# SDConnection.net
KiCad netlist of a schematic drawn in Altium Designer
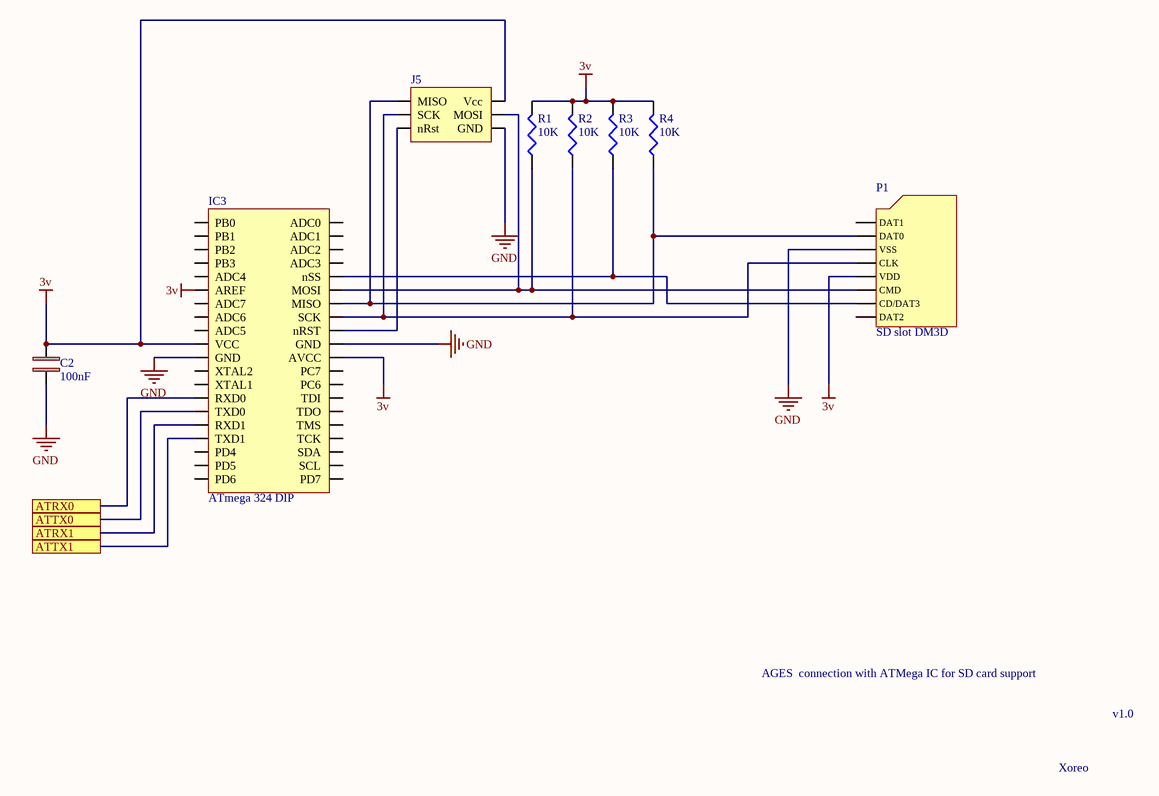
[diagram p0: SDConnection.SchDoc]

(export (version "E")
  (design (tool "Eeschema 10.0.6"))
  (components
    (comp (ref "C2")
      (value "100nF")
      (footprint "CAPACITOR 1206")
      (description "Ceramic capacitor SMD-1206 100nF /50V X7R# K +-10%, AVX, RoHS, /4000 reel/")
      (fields
        (field (name "MANUFACTURER") "Kyocera AVX")
        (field (name "MANUFACTURER PART NUMBER") "12065C104KAT2A")
      )
      (libsource (lib "SD-Module-SCH-LIB") (part "Capacitor{colon} 100nF"))
    )
    (comp (ref "IC3")
      (value "ATmega 324 DIP")
      (footprint "DIP40 HDR")
      (description "8-bit AVR MCU, 32 KB, 2048 Bytes, 20 MHz, 1.8 to 5.5V, PDIP-40, RoHS")
      (fields
        (field (name "MANUFACTURER") "Microchip")
        (field (name "MANUFACTURER PART NUMBER") "ATMEGA324PA-PU")
      )
      (libsource (lib "SD-Module-SCH-LIB") (part "IC{colon} ATmega324"))
    )
    (comp (ref "J5")
      (value "2x3 male pin header")
      (footprint "2X3 HDR")
      (description "2x3 Pin header")
      (libsource (lib "SD-Module-SCH-LIB") (part "Connector{colon} 2x3 Pin"))
    )
    (comp (ref "P1")
      (value "SD slot DM3D")
      (footprint "SD SLOT")
      (description "Memory Card Connectors MICRO SD CD CONN STD SMT PUSHPULL")
      (fields (field (name "MANUFACTURER") "Hirose") (field (name "MANUFACTURER PART NUMBER") "DM3D-SF"))
      (libsource (lib "SD-Module-SCH-LIB") (part "SD slot"))
    )
    (comp (ref "R1")
      (value "10K")
      (footprint "RESISTOR 0805")
      (description "Res Thick Film 0805 10K Ohm 5% 1/8W ±200ppm/°C Molded SMD SMD Paper T/R")
      (fields
        (field (name "MANUFACTURER") "Vishay Dale")
        (field (name "MANUFACTURER PART NUMBER") "CRCW080510K0JNEB")
      )
      (libsource (lib "SD-Module-SCH-LIB") (part "Resistor{colon} 10K R"))
    )
    (comp (ref "R2")
      (value "10K")
      (footprint "RESISTOR 0805")
      (description "Res Thick Film 0805 10K Ohm 5% 1/8W ±200ppm/°C Molded SMD SMD Paper T/R")
      (fields
        (field (name "MANUFACTURER") "Vishay Dale")
        (field (name "MANUFACTURER PART NUMBER") "CRCW080510K0JNEB")
      )
      (libsource (lib "SD-Module-SCH-LIB") (part "Resistor{colon} 10K R"))
    )
    (comp (ref "R3")
      (value "10K")
      (footprint "RESISTOR 0805")
      (description "Res Thick Film 0805 10K Ohm 5% 1/8W ±200ppm/°C Molded SMD SMD Paper T/R")
      (fields
        (field (name "MANUFACTURER") "Vishay Dale")
        (field (name "MANUFACTURER PART NUMBER") "CRCW080510K0JNEB")
      )
      (libsource (lib "SD-Module-SCH-LIB") (part "Resistor{colon} 10K R"))
    )
    (comp (ref "R4")
      (value "10K")
      (footprint "RESISTOR 0805")
      (description "Res Thick Film 0805 10K Ohm 5% 1/8W ±200ppm/°C Molded SMD SMD Paper T/R")
      (fields
        (field (name "MANUFACTURER") "Vishay Dale")
        (field (name "MANUFACTURER PART NUMBER") "CRCW080510K0JNEB")
      )
      (libsource (lib "SD-Module-SCH-LIB") (part "Resistor{colon} 10K R"))
    )
  )
  (nets
    (net (code "1") (name "/ATRX0") (class "Default")
      (node (ref "IC3") (pin "14") (pinfunction "RXD0_14") (pintype "passive"))
    )
    (net (code "2") (name "/ATRX1") (class "Default")
      (node (ref "IC3") (pin "16") (pinfunction "RXD1_16") (pintype "passive"))
    )
    (net (code "3") (name "/ATTX0") (class "Default")
      (node (ref "IC3") (pin "15") (pinfunction "TXD0_15") (pintype "passive"))
    )
    (net (code "4") (name "/ATTX1") (class "Default")
      (node (ref "IC3") (pin "17") (pinfunction "TXD1_17") (pintype "passive"))
    )
    (net (code "5") (name "3v") (class "Default")
      (node (ref "C2") (pin "1") (pinfunction "1_1") (pintype "passive"))
      (node (ref "IC3") (pin "10") (pinfunction "VCC_10") (pintype "passive"))
      (node (ref "IC3") (pin "30") (pinfunction "AVCC_30") (pintype "passive"))
      (node (ref "IC3") (pin "32") (pinfunction "AREF_32") (pintype "passive"))
      (node (ref "J5") (pin "2") (pinfunction "Vcc_2") (pintype "passive"))
      (node (ref "P1") (pin "4") (pinfunction "VDD_4") (pintype "passive"))
      (node (ref "R1") (pin "2") (pinfunction "2_2") (pintype "passive"))
      (node (ref "R2") (pin "2") (pinfunction "2_2") (pintype "passive"))
      (node (ref "R3") (pin "2") (pinfunction "2_2") (pintype "passive"))
      (node (ref "R4") (pin "2") (pinfunction "2_2") (pintype "passive"))
    )
    (net (code "6") (name "GND") (class "Default")
      (node (ref "C2") (pin "2") (pinfunction "2_2") (pintype "passive"))
      (node (ref "IC3") (pin "11") (pinfunction "GND_11") (pintype "passive"))
      (node (ref "IC3") (pin "31") (pinfunction "GND_31") (pintype "passive"))
      (node (ref "J5") (pin "6") (pinfunction "GND_6") (pintype "passive"))
      (node (ref "P1") (pin "6") (pinfunction "VSS_6") (pintype "passive"))
    )
    (net (code "7") (name "Net-(IC3-MISO)") (class "Default")
      (node (ref "IC3") (pin "7") (pinfunction "MISO_7") (pintype "passive"))
      (node (ref "J5") (pin "1") (pinfunction "MISO_1") (pintype "passive"))
      (node (ref "P1") (pin "7") (pinfunction "DAT0_7") (pintype "passive"))
      (node (ref "R4") (pin "1") (pinfunction "1_1") (pintype "passive"))
    )
    (net (code "8") (name "Net-(IC3-MOSI)") (class "Default")
      (node (ref "IC3") (pin "6") (pinfunction "MOSI_6") (pintype "passive"))
      (node (ref "J5") (pin "4") (pinfunction "MOSI_4") (pintype "passive"))
      (node (ref "P1") (pin "3") (pinfunction "CMD_3") (pintype "passive"))
      (node (ref "R1") (pin "1") (pinfunction "1_1") (pintype "passive"))
    )
    (net (code "9") (name "Net-(IC3-SCK)") (class "Default")
      (node (ref "IC3") (pin "8") (pinfunction "SCK_8") (pintype "passive"))
      (node (ref "J5") (pin "3") (pinfunction "SCK_3") (pintype "passive"))
      (node (ref "P1") (pin "5") (pinfunction "CLK_5") (pintype "passive"))
      (node (ref "R2") (pin "1") (pinfunction "1_1") (pintype "passive"))
    )
    (net (code "10") (name "Net-(IC3-nRST)") (class "Default")
      (node (ref "IC3") (pin "9") (pinfunction "nRST_9") (pintype "passive"))
      (node (ref "J5") (pin "5") (pinfunction "nRst_5") (pintype "passive"))
    )
    (net (code "11") (name "Net-(IC3-nSS)") (class "Default")
      (node (ref "IC3") (pin "5") (pinfunction "nSS_5") (pintype "passive"))
      (node (ref "P1") (pin "2") (pinfunction "CD/DAT3_2") (pintype "passive"))
      (node (ref "R3") (pin "1") (pinfunction "1_1") (pintype "passive"))
    )
    (net (code "12") (name "unconnected-(IC3-ADC0-Pad40)") (class "Default")
      (node (ref "IC3") (pin "40") (pinfunction "ADC0_40") (pintype "passive"))
    )
    (net (code "13") (name "unconnected-(IC3-ADC1-Pad39)") (class "Default")
      (node (ref "IC3") (pin "39") (pinfunction "ADC1_39") (pintype "passive"))
    )
    (net (code "14") (name "unconnected-(IC3-ADC2-Pad38)") (class "Default")
      (node (ref "IC3") (pin "38") (pinfunction "ADC2_38") (pintype "passive"))
    )
    (net (code "15") (name "unconnected-(IC3-ADC3-Pad37)") (class "Default")
      (node (ref "IC3") (pin "37") (pinfunction "ADC3_37") (pintype "passive"))
    )
    (net (code "16") (name "unconnected-(IC3-ADC4-Pad36)") (class "Default")
      (node (ref "IC3") (pin "36") (pinfunction "ADC4_36") (pintype "passive"))
    )
    (net (code "17") (name "unconnected-(IC3-ADC5-Pad35)") (class "Default")
      (node (ref "IC3") (pin "35") (pinfunction "ADC5_35") (pintype "passive"))
    )
    (net (code "18") (name "unconnected-(IC3-ADC6-Pad34)") (class "Default")
      (node (ref "IC3") (pin "34") (pinfunction "ADC6_34") (pintype "passive"))
    )
    (net (code "19") (name "unconnected-(IC3-ADC7-Pad33)") (class "Default")
      (node (ref "IC3") (pin "33") (pinfunction "ADC7_33") (pintype "passive"))
    )
    (net (code "20") (name "unconnected-(IC3-PB0-Pad1)") (class "Default")
      (node (ref "IC3") (pin "1") (pinfunction "PB0_1") (pintype "passive"))
    )
    (net (code "21") (name "unconnected-(IC3-PB1-Pad2)") (class "Default")
      (node (ref "IC3") (pin "2") (pinfunction "PB1_2") (pintype "passive"))
    )
    (net (code "22") (name "unconnected-(IC3-PB2-Pad3)") (class "Default")
      (node (ref "IC3") (pin "3") (pinfunction "PB2_3") (pintype "passive"))
    )
    (net (code "23") (name "unconnected-(IC3-PB3-Pad4)") (class "Default")
      (node (ref "IC3") (pin "4") (pinfunction "PB3_4") (pintype "passive"))
    )
    (net (code "24") (name "unconnected-(IC3-PC6-Pad28)") (class "Default")
      (node (ref "IC3") (pin "28") (pinfunction "PC6_28") (pintype "passive"))
    )
    (net (code "25") (name "unconnected-(IC3-PC7-Pad29)") (class "Default")
      (node (ref "IC3") (pin "29") (pinfunction "PC7_29") (pintype "passive"))
    )
    (net (code "26") (name "unconnected-(IC3-PD4-Pad18)") (class "Default")
      (node (ref "IC3") (pin "18") (pinfunction "PD4_18") (pintype "passive"))
    )
    (net (code "27") (name "unconnected-(IC3-PD5-Pad19)") (class "Default")
      (node (ref "IC3") (pin "19") (pinfunction "PD5_19") (pintype "passive"))
    )
    (net (code "28") (name "unconnected-(IC3-PD6-Pad20)") (class "Default")
      (node (ref "IC3") (pin "20") (pinfunction "PD6_20") (pintype "passive"))
    )
    (net (code "29") (name "unconnected-(IC3-PD7-Pad21)") (class "Default")
      (node (ref "IC3") (pin "21") (pinfunction "PD7_21") (pintype "passive"))
    )
    (net (code "30") (name "unconnected-(IC3-SCL-Pad22)") (class "Default")
      (node (ref "IC3") (pin "22") (pinfunction "SCL_22") (pintype "passive"))
    )
    (net (code "31") (name "unconnected-(IC3-SDA-Pad23)") (class "Default")
      (node (ref "IC3") (pin "23") (pinfunction "SDA_23") (pintype "passive"))
    )
    (net (code "32") (name "unconnected-(IC3-TCK-Pad24)") (class "Default")
      (node (ref "IC3") (pin "24") (pinfunction "TCK_24") (pintype "passive"))
    )
    (net (code "33") (name "unconnected-(IC3-TDI-Pad27)") (class "Default")
      (node (ref "IC3") (pin "27") (pinfunction "TDI_27") (pintype "passive"))
    )
    (net (code "34") (name "unconnected-(IC3-TDO-Pad26)") (class "Default")
      (node (ref "IC3") (pin "26") (pinfunction "TDO_26") (pintype "passive"))
    )
    (net (code "35") (name "unconnected-(IC3-TMS-Pad25)") (class "Default")
      (node (ref "IC3") (pin "25") (pinfunction "TMS_25") (pintype "passive"))
    )
    (net (code "36") (name "unconnected-(IC3-XTAL1-Pad13)") (class "Default")
      (node (ref "IC3") (pin "13") (pinfunction "XTAL1_13") (pintype "passive"))
    )
    (net (code "37") (name "unconnected-(IC3-XTAL2-Pad12)") (class "Default")
      (node (ref "IC3") (pin "12") (pinfunction "XTAL2_12") (pintype "passive"))
    )
    (net (code "38") (name "unconnected-(P1-DAT1-Pad8)") (class "Default")
      (node (ref "P1") (pin "8") (pinfunction "DAT1_8") (pintype "passive"))
    )
    (net (code "39") (name "unconnected-(P1-DAT2-Pad1)") (class "Default")
      (node (ref "P1") (pin "1") (pinfunction "DAT2_1") (pintype "passive"))
    )
  )
)
